# pccasefanctrlx8.net
KiCad netlist of a schematic drawn in EAGLE
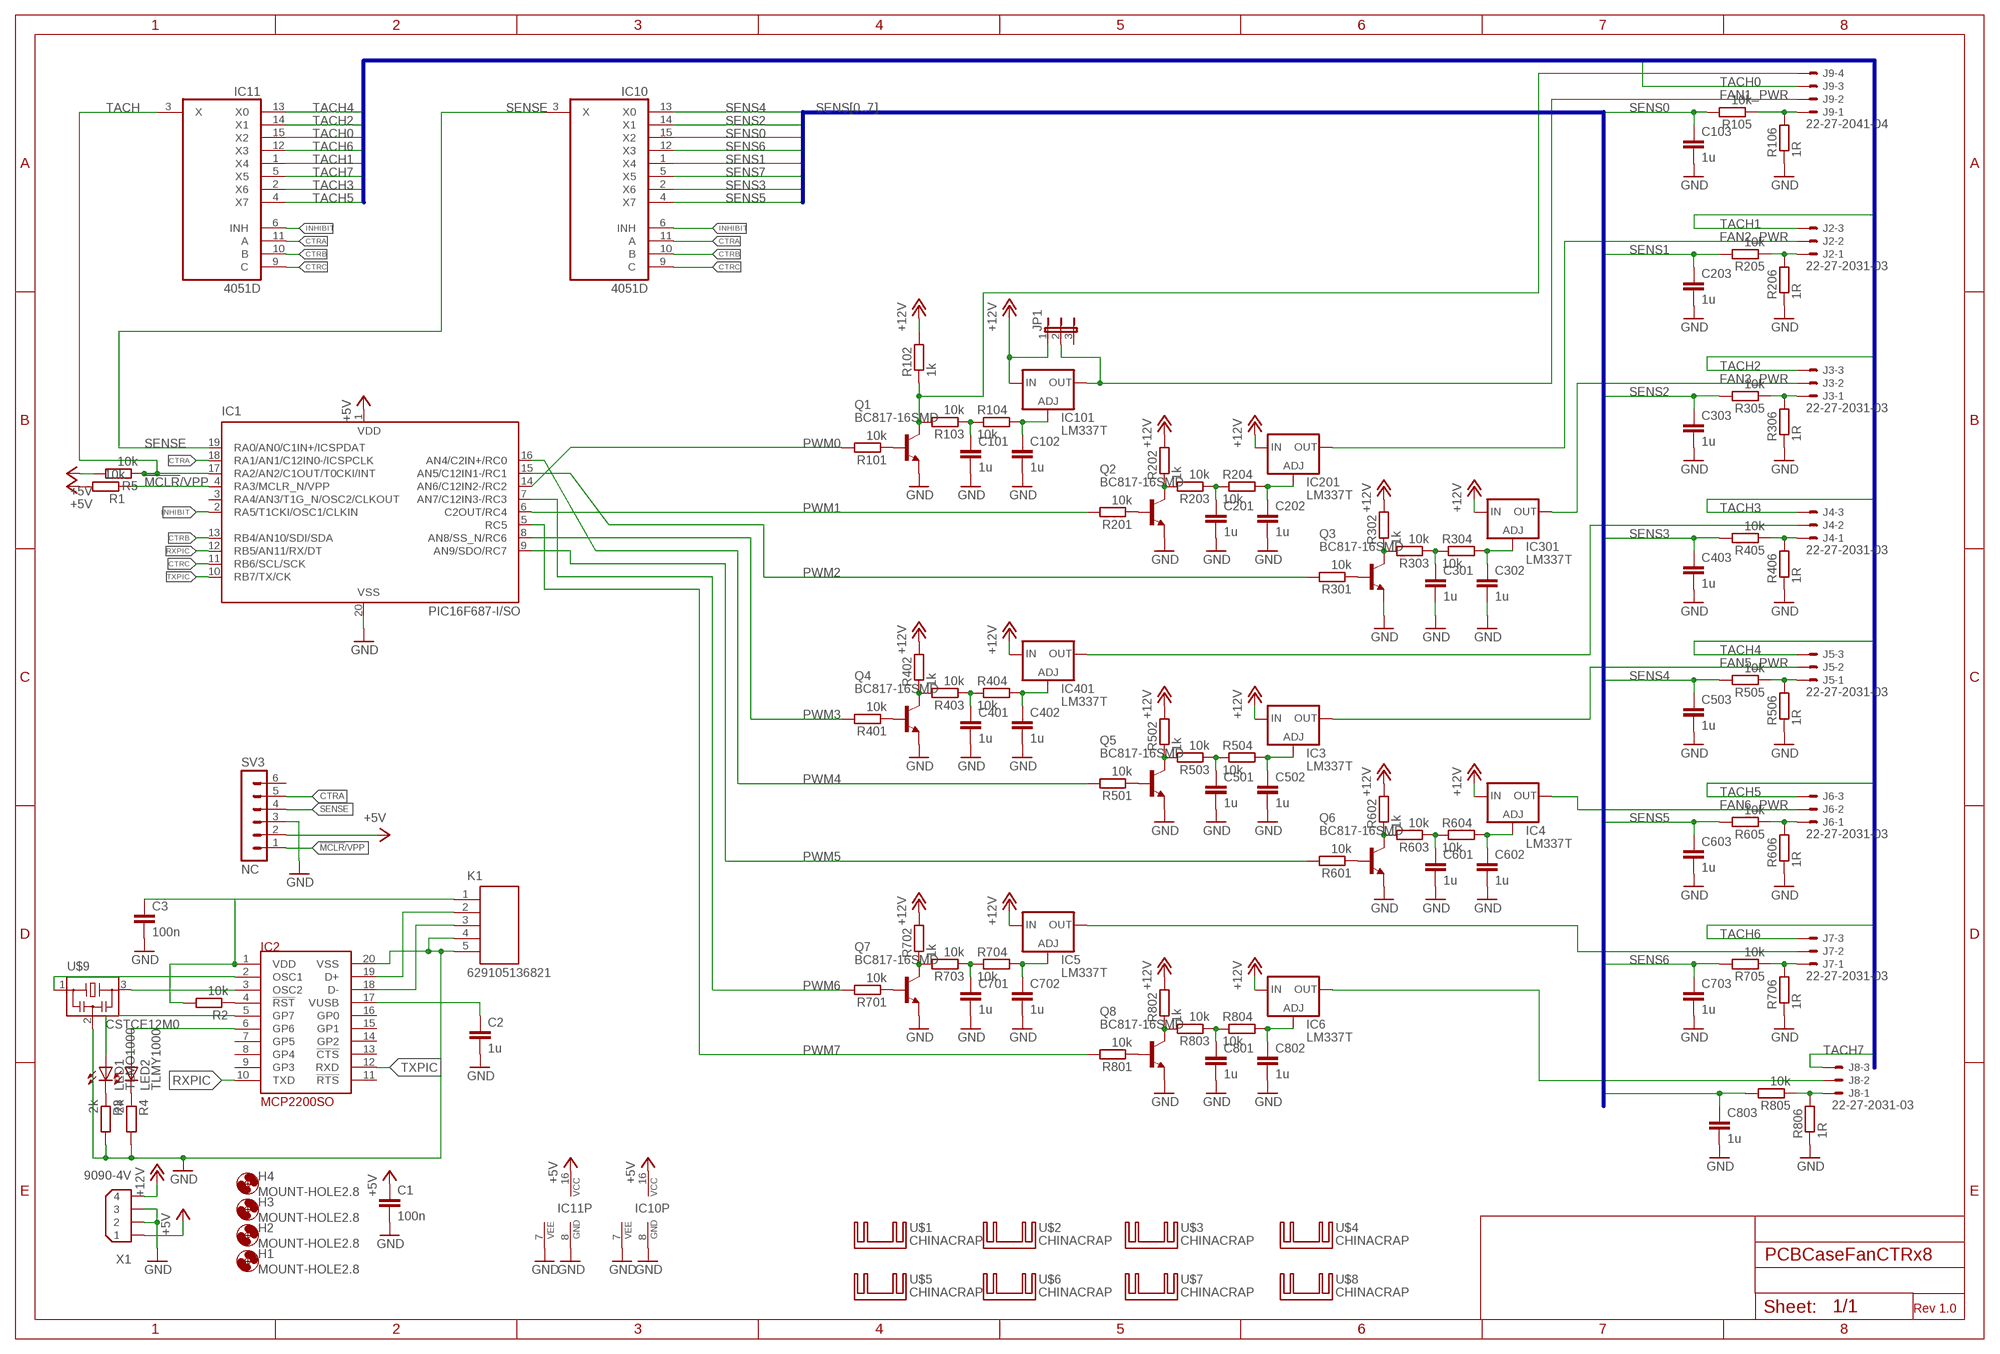
[diagram p0: schematic, sheet 1]

(export (version "E")
  (design (tool "Eeschema 10.0.6"))
  (components
    (comp (ref "C1")
      (value "100n")
      (footprint "eagle-import:C0603K")
      (libsource (lib "eagle-import") (part "C-EUC0603K"))
    )
    (comp (ref "C2")
      (value "1u")
      (footprint "eagle-import:C0603K")
      (libsource (lib "eagle-import") (part "C-EUC0603K"))
    )
    (comp (ref "C3")
      (value "100n")
      (footprint "eagle-import:C0603K")
      (libsource (lib "eagle-import") (part "C-EUC0603K"))
    )
    (comp (ref "C101")
      (value "1u")
      (footprint "eagle-import:C0603K")
      (libsource (lib "eagle-import") (part "C-EUC0603K"))
    )
    (comp (ref "C102")
      (value "1u")
      (footprint "eagle-import:C0603K")
      (libsource (lib "eagle-import") (part "C-EUC0603K"))
    )
    (comp (ref "C103")
      (value "1u")
      (footprint "eagle-import:C0603K")
      (libsource (lib "eagle-import") (part "C-EUC0603K"))
    )
    (comp (ref "C201")
      (value "1u")
      (footprint "eagle-import:C0603K")
      (libsource (lib "eagle-import") (part "C-EUC0603K"))
    )
    (comp (ref "C202")
      (value "1u")
      (footprint "eagle-import:C0603K")
      (libsource (lib "eagle-import") (part "C-EUC0603K"))
    )
    (comp (ref "C203")
      (value "1u")
      (footprint "eagle-import:C0603K")
      (libsource (lib "eagle-import") (part "C-EUC0603K"))
    )
    (comp (ref "C301")
      (value "1u")
      (footprint "eagle-import:C0603K")
      (libsource (lib "eagle-import") (part "C-EUC0603K"))
    )
    (comp (ref "C302")
      (value "1u")
      (footprint "eagle-import:C0603K")
      (libsource (lib "eagle-import") (part "C-EUC0603K"))
    )
    (comp (ref "C303")
      (value "1u")
      (footprint "eagle-import:C0603K")
      (libsource (lib "eagle-import") (part "C-EUC0603K"))
    )
    (comp (ref "C401")
      (value "1u")
      (footprint "eagle-import:C0603K")
      (libsource (lib "eagle-import") (part "C-EUC0603K"))
    )
    (comp (ref "C402")
      (value "1u")
      (footprint "eagle-import:C0603K")
      (libsource (lib "eagle-import") (part "C-EUC0603K"))
    )
    (comp (ref "C403")
      (value "1u")
      (footprint "eagle-import:C0603K")
      (libsource (lib "eagle-import") (part "C-EUC0603K"))
    )
    (comp (ref "C501")
      (value "1u")
      (footprint "eagle-import:C0603K")
      (libsource (lib "eagle-import") (part "C-EUC0603K"))
    )
    (comp (ref "C502")
      (value "1u")
      (footprint "eagle-import:C0603K")
      (libsource (lib "eagle-import") (part "C-EUC0603K"))
    )
    (comp (ref "C503")
      (value "1u")
      (footprint "eagle-import:C0603K")
      (libsource (lib "eagle-import") (part "C-EUC0603K"))
    )
    (comp (ref "C601")
      (value "1u")
      (footprint "eagle-import:C0603K")
      (libsource (lib "eagle-import") (part "C-EUC0603K"))
    )
    (comp (ref "C602")
      (value "1u")
      (footprint "eagle-import:C0603K")
      (libsource (lib "eagle-import") (part "C-EUC0603K"))
    )
    (comp (ref "C603")
      (value "1u")
      (footprint "eagle-import:C0603K")
      (libsource (lib "eagle-import") (part "C-EUC0603K"))
    )
    (comp (ref "C701")
      (value "1u")
      (footprint "eagle-import:C0603K")
      (libsource (lib "eagle-import") (part "C-EUC0603K"))
    )
    (comp (ref "C702")
      (value "1u")
      (footprint "eagle-import:C0603K")
      (libsource (lib "eagle-import") (part "C-EUC0603K"))
    )
    (comp (ref "C703")
      (value "1u")
      (footprint "eagle-import:C0603K")
      (libsource (lib "eagle-import") (part "C-EUC0603K"))
    )
    (comp (ref "C801")
      (value "1u")
      (footprint "eagle-import:C0603K")
      (libsource (lib "eagle-import") (part "C-EUC0603K"))
    )
    (comp (ref "C802")
      (value "1u")
      (footprint "eagle-import:C0603K")
      (libsource (lib "eagle-import") (part "C-EUC0603K"))
    )
    (comp (ref "C803")
      (value "1u")
      (footprint "eagle-import:C0603K")
      (libsource (lib "eagle-import") (part "C-EUC0603K"))
    )
    (comp (ref "H1")
      (value "MOUNT-HOLE2.8")
      (footprint "eagle-import:2,8")
      (libsource (lib "eagle-import") (part "MOUNT-HOLE2.8"))
    )
    (comp (ref "H2")
      (value "MOUNT-HOLE2.8")
      (footprint "eagle-import:2,8")
      (libsource (lib "eagle-import") (part "MOUNT-HOLE2.8"))
    )
    (comp (ref "H3")
      (value "MOUNT-HOLE2.8")
      (footprint "eagle-import:2,8")
      (libsource (lib "eagle-import") (part "MOUNT-HOLE2.8"))
    )
    (comp (ref "H4")
      (value "MOUNT-HOLE2.8")
      (footprint "eagle-import:2,8")
      (libsource (lib "eagle-import") (part "MOUNT-HOLE2.8"))
    )
    (comp (ref "IC1")
      (value "PIC16F687-I/SO")
      (footprint "eagle-import:SO-20W")
      (libsource (lib "eagle-import") (part "PIC16F687-I/SO"))
    )
    (comp (ref "IC2")
      (value "MCP2200SO")
      (footprint "eagle-import:SO-20W")
      (libsource (lib "eagle-import") (part "MCP2200SO"))
    )
    (comp (ref "IC3")
      (value "LM337T")
      (footprint "eagle-import:317TS")
      (libsource (lib "eagle-import") (part "LM317TS"))
    )
    (comp (ref "IC4")
      (value "LM337T")
      (footprint "eagle-import:317TS")
      (libsource (lib "eagle-import") (part "LM317TS"))
    )
    (comp (ref "IC5")
      (value "LM337T")
      (footprint "eagle-import:317TS")
      (libsource (lib "eagle-import") (part "LM317TS"))
    )
    (comp (ref "IC6")
      (value "LM337T")
      (footprint "eagle-import:317TS")
      (libsource (lib "eagle-import") (part "LM317TS"))
    )
    (comp (ref "IC10")
      (value "4051D")
      (footprint "eagle-import:SO16")
      (libsource (lib "eagle-import") (part "4051D"))
    )
    (comp (ref "IC11")
      (value "4051D")
      (footprint "eagle-import:SO16")
      (libsource (lib "eagle-import") (part "4051D"))
    )
    (comp (ref "IC101")
      (value "LM337T")
      (footprint "eagle-import:317TS")
      (libsource (lib "eagle-import") (part "LM317TS"))
    )
    (comp (ref "IC201")
      (value "LM337T")
      (footprint "eagle-import:317TS")
      (libsource (lib "eagle-import") (part "LM317TS"))
    )
    (comp (ref "IC301")
      (value "LM337T")
      (footprint "eagle-import:317TS")
      (libsource (lib "eagle-import") (part "LM317TS"))
    )
    (comp (ref "IC401")
      (value "LM337T")
      (footprint "eagle-import:317TS")
      (libsource (lib "eagle-import") (part "LM317TS"))
    )
    (comp (ref "J2")
      (value "22-27-2031-03")
      (footprint "eagle-import:6410-03")
      (libsource (lib "eagle-import") (part "22-?-0327-2031"))
    )
    (comp (ref "J3")
      (value "22-27-2031-03")
      (footprint "eagle-import:6410-03")
      (libsource (lib "eagle-import") (part "22-?-0327-2031"))
    )
    (comp (ref "J4")
      (value "22-27-2031-03")
      (footprint "eagle-import:6410-03")
      (libsource (lib "eagle-import") (part "22-?-0327-2031"))
    )
    (comp (ref "J5")
      (value "22-27-2031-03")
      (footprint "eagle-import:6410-03")
      (libsource (lib "eagle-import") (part "22-?-0327-2031"))
    )
    (comp (ref "J6")
      (value "22-27-2031-03")
      (footprint "eagle-import:6410-03")
      (libsource (lib "eagle-import") (part "22-?-0327-2031"))
    )
    (comp (ref "J7")
      (value "22-27-2031-03")
      (footprint "eagle-import:6410-03")
      (libsource (lib "eagle-import") (part "22-?-0327-2031"))
    )
    (comp (ref "J8")
      (value "22-27-2031-03")
      (footprint "eagle-import:6410-03")
      (libsource (lib "eagle-import") (part "22-?-0327-2031"))
    )
    (comp (ref "J9")
      (value "22-27-2041-04")
      (footprint "eagle-import:6410-04")
      (libsource (lib "eagle-import") (part "22-?-0427-2041"))
    )
    (comp (ref "JP1")
      (value "JP2E")
      (footprint "eagle-import:JP2")
      (libsource (lib "eagle-import") (part "JP2E"))
    )
    (comp (ref "K1")
      (value "629105136821")
      (footprint "eagle-import:629105136821")
      (libsource (lib "eagle-import") (part "629105136821"))
    )
    (comp (ref "LED1")
      (value "TLMO1000")
      (footprint "eagle-import:SML0603")
      (libsource (lib "eagle-import") (part "LEDSML0603"))
    )
    (comp (ref "LED2")
      (value "TLMY1000")
      (footprint "eagle-import:SML0603")
      (libsource (lib "eagle-import") (part "LEDSML0603"))
    )
    (comp (ref "Q1")
      (value "BC817-16SMD")
      (footprint "eagle-import:SOT23-BEC")
      (libsource (lib "eagle-import") (part "BC817SMD-16"))
    )
    (comp (ref "Q2")
      (value "BC817-16SMD")
      (footprint "eagle-import:SOT23-BEC")
      (libsource (lib "eagle-import") (part "BC817SMD-16"))
    )
    (comp (ref "Q3")
      (value "BC817-16SMD")
      (footprint "eagle-import:SOT23-BEC")
      (libsource (lib "eagle-import") (part "BC817SMD-16"))
    )
    (comp (ref "Q4")
      (value "BC817-16SMD")
      (footprint "eagle-import:SOT23-BEC")
      (libsource (lib "eagle-import") (part "BC817SMD-16"))
    )
    (comp (ref "Q5")
      (value "BC817-16SMD")
      (footprint "eagle-import:SOT23-BEC")
      (libsource (lib "eagle-import") (part "BC817SMD-16"))
    )
    (comp (ref "Q6")
      (value "BC817-16SMD")
      (footprint "eagle-import:SOT23-BEC")
      (libsource (lib "eagle-import") (part "BC817SMD-16"))
    )
    (comp (ref "Q7")
      (value "BC817-16SMD")
      (footprint "eagle-import:SOT23-BEC")
      (libsource (lib "eagle-import") (part "BC817SMD-16"))
    )
    (comp (ref "Q8")
      (value "BC817-16SMD")
      (footprint "eagle-import:SOT23-BEC")
      (libsource (lib "eagle-import") (part "BC817SMD-16"))
    )
    (comp (ref "R1")
      (value "10k")
      (footprint "eagle-import:R0603")
      (libsource (lib "eagle-import") (part "R-EU_R0603"))
    )
    (comp (ref "R2")
      (value "10k")
      (footprint "eagle-import:R0603")
      (libsource (lib "eagle-import") (part "R-EU_R0603"))
    )
    (comp (ref "R3")
      (value "2k")
      (footprint "eagle-import:R0603")
      (libsource (lib "eagle-import") (part "R-EU_R0603"))
    )
    (comp (ref "R4")
      (value "2k")
      (footprint "eagle-import:R0603")
      (libsource (lib "eagle-import") (part "R-EU_R0603"))
    )
    (comp (ref "R5")
      (value "10k")
      (footprint "eagle-import:R0603")
      (libsource (lib "eagle-import") (part "R-EU_R0603"))
    )
    (comp (ref "R101")
      (value "10k")
      (footprint "eagle-import:R0603")
      (libsource (lib "eagle-import") (part "R-EU_R0603"))
    )
    (comp (ref "R102")
      (value "1k")
      (footprint "eagle-import:R0603")
      (libsource (lib "eagle-import") (part "R-EU_R0603"))
    )
    (comp (ref "R103")
      (value "10k")
      (footprint "eagle-import:R0603")
      (libsource (lib "eagle-import") (part "R-EU_R0603"))
    )
    (comp (ref "R104")
      (value "10k")
      (footprint "eagle-import:R0603")
      (libsource (lib "eagle-import") (part "R-EU_R0603"))
    )
    (comp (ref "R105")
      (value "10k")
      (footprint "eagle-import:R0603")
      (libsource (lib "eagle-import") (part "R-EU_R0603"))
    )
    (comp (ref "R106")
      (value "1R")
      (footprint "eagle-import:P0613V")
      (libsource (lib "eagle-import") (part "R-EU_0613/5V"))
    )
    (comp (ref "R201")
      (value "10k")
      (footprint "eagle-import:R0603")
      (libsource (lib "eagle-import") (part "R-EU_R0603"))
    )
    (comp (ref "R202")
      (value "1k")
      (footprint "eagle-import:R0603")
      (libsource (lib "eagle-import") (part "R-EU_R0603"))
    )
    (comp (ref "R203")
      (value "10k")
      (footprint "eagle-import:R0603")
      (libsource (lib "eagle-import") (part "R-EU_R0603"))
    )
    (comp (ref "R204")
      (value "10k")
      (footprint "eagle-import:R0603")
      (libsource (lib "eagle-import") (part "R-EU_R0603"))
    )
    (comp (ref "R205")
      (value "10k")
      (footprint "eagle-import:R0603")
      (libsource (lib "eagle-import") (part "R-EU_R0603"))
    )
    (comp (ref "R206")
      (value "1R")
      (footprint "eagle-import:P0613V")
      (libsource (lib "eagle-import") (part "R-EU_0613/5V"))
    )
    (comp (ref "R301")
      (value "10k")
      (footprint "eagle-import:R0603")
      (libsource (lib "eagle-import") (part "R-EU_R0603"))
    )
    (comp (ref "R302")
      (value "1k")
      (footprint "eagle-import:R0603")
      (libsource (lib "eagle-import") (part "R-EU_R0603"))
    )
    (comp (ref "R303")
      (value "10k")
      (footprint "eagle-import:R0603")
      (libsource (lib "eagle-import") (part "R-EU_R0603"))
    )
    (comp (ref "R304")
      (value "10k")
      (footprint "eagle-import:R0603")
      (libsource (lib "eagle-import") (part "R-EU_R0603"))
    )
    (comp (ref "R305")
      (value "10k")
      (footprint "eagle-import:R0603")
      (libsource (lib "eagle-import") (part "R-EU_R0603"))
    )
    (comp (ref "R306")
      (value "1R")
      (footprint "eagle-import:P0613V")
      (libsource (lib "eagle-import") (part "R-EU_0613/5V"))
    )
    (comp (ref "R401")
      (value "10k")
      (footprint "eagle-import:R0603")
      (libsource (lib "eagle-import") (part "R-EU_R0603"))
    )
    (comp (ref "R402")
      (value "1k")
      (footprint "eagle-import:R0603")
      (libsource (lib "eagle-import") (part "R-EU_R0603"))
    )
    (comp (ref "R403")
      (value "10k")
      (footprint "eagle-import:R0603")
      (libsource (lib "eagle-import") (part "R-EU_R0603"))
    )
    (comp (ref "R404")
      (value "10k")
      (footprint "eagle-import:R0603")
      (libsource (lib "eagle-import") (part "R-EU_R0603"))
    )
    (comp (ref "R405")
      (value "10k")
      (footprint "eagle-import:R0603")
      (libsource (lib "eagle-import") (part "R-EU_R0603"))
    )
    (comp (ref "R406")
      (value "1R")
      (footprint "eagle-import:P0613V")
      (libsource (lib "eagle-import") (part "R-EU_0613/5V"))
    )
    (comp (ref "R501")
      (value "10k")
      (footprint "eagle-import:R0603")
      (libsource (lib "eagle-import") (part "R-EU_R0603"))
    )
    (comp (ref "R502")
      (value "1k")
      (footprint "eagle-import:R0603")
      (libsource (lib "eagle-import") (part "R-EU_R0603"))
    )
    (comp (ref "R503")
      (value "10k")
      (footprint "eagle-import:R0603")
      (libsource (lib "eagle-import") (part "R-EU_R0603"))
    )
    (comp (ref "R504")
      (value "10k")
      (footprint "eagle-import:R0603")
      (libsource (lib "eagle-import") (part "R-EU_R0603"))
    )
    (comp (ref "R505")
      (value "10k")
      (footprint "eagle-import:R0603")
      (libsource (lib "eagle-import") (part "R-EU_R0603"))
    )
    (comp (ref "R506")
      (value "1R")
      (footprint "eagle-import:P0613V")
      (libsource (lib "eagle-import") (part "R-EU_0613/5V"))
    )
    (comp (ref "R601")
      (value "10k")
      (footprint "eagle-import:R0603")
      (libsource (lib "eagle-import") (part "R-EU_R0603"))
    )
    (comp (ref "R602")
      (value "1k")
      (footprint "eagle-import:R0603")
      (libsource (lib "eagle-import") (part "R-EU_R0603"))
    )
    (comp (ref "R603")
      (value "10k")
      (footprint "eagle-import:R0603")
      (libsource (lib "eagle-import") (part "R-EU_R0603"))
    )
    (comp (ref "R604")
      (value "10k")
      (footprint "eagle-import:R0603")
      (libsource (lib "eagle-import") (part "R-EU_R0603"))
    )
    (comp (ref "R605")
      (value "10k")
      (footprint "eagle-import:R0603")
      (libsource (lib "eagle-import") (part "R-EU_R0603"))
    )
    (comp (ref "R606")
      (value "1R")
      (footprint "eagle-import:P0613V")
      (libsource (lib "eagle-import") (part "R-EU_0613/5V"))
    )
    (comp (ref "R701")
      (value "10k")
      (footprint "eagle-import:R0603")
      (libsource (lib "eagle-import") (part "R-EU_R0603"))
    )
    (comp (ref "R702")
      (value "1k")
      (footprint "eagle-import:R0603")
      (libsource (lib "eagle-import") (part "R-EU_R0603"))
    )
    (comp (ref "R703")
      (value "10k")
      (footprint "eagle-import:R0603")
      (libsource (lib "eagle-import") (part "R-EU_R0603"))
    )
    (comp (ref "R704")
      (value "10k")
      (footprint "eagle-import:R0603")
      (libsource (lib "eagle-import") (part "R-EU_R0603"))
    )
    (comp (ref "R705")
      (value "10k")
      (footprint "eagle-import:R0603")
      (libsource (lib "eagle-import") (part "R-EU_R0603"))
    )
    (comp (ref "R706")
      (value "1R")
      (footprint "eagle-import:P0613V")
      (libsource (lib "eagle-import") (part "R-EU_0613/5V"))
    )
    (comp (ref "R801")
      (value "10k")
      (footprint "eagle-import:R0603")
      (libsource (lib "eagle-import") (part "R-EU_R0603"))
    )
    (comp (ref "R802")
      (value "1k")
      (footprint "eagle-import:R0603")
      (libsource (lib "eagle-import") (part "R-EU_R0603"))
    )
    (comp (ref "R803")
      (value "10k")
      (footprint "eagle-import:R0603")
      (libsource (lib "eagle-import") (part "R-EU_R0603"))
    )
    (comp (ref "R804")
      (value "10k")
      (footprint "eagle-import:R0603")
      (libsource (lib "eagle-import") (part "R-EU_R0603"))
    )
    (comp (ref "R805")
      (value "10k")
      (footprint "eagle-import:R0603")
      (libsource (lib "eagle-import") (part "R-EU_R0603"))
    )
    (comp (ref "R806")
      (value "1R")
      (footprint "eagle-import:P0613V")
      (libsource (lib "eagle-import") (part "R-EU_0613/5V"))
    )
    (comp (ref "SV3")
      (value "NC")
      (footprint "eagle-import:MA06-1")
      (libsource (lib "eagle-import") (part "MA06-1"))
    )
    (comp (ref "U$1")
      (value "CHINACRAP")
      (footprint "eagle-import:MYCHINACRAP")
      (libsource (lib "eagle-import") (part "CHINACRAP"))
    )
    (comp (ref "U$2")
      (value "CHINACRAP")
      (footprint "eagle-import:MYCHINACRAP")
      (libsource (lib "eagle-import") (part "CHINACRAP"))
    )
    (comp (ref "U$3")
      (value "CHINACRAP")
      (footprint "eagle-import:MYCHINACRAP")
      (libsource (lib "eagle-import") (part "CHINACRAP"))
    )
    (comp (ref "U$4")
      (value "CHINACRAP")
      (footprint "eagle-import:MYCHINACRAP")
      (libsource (lib "eagle-import") (part "CHINACRAP"))
    )
    (comp (ref "U$5")
      (value "CHINACRAP")
      (footprint "eagle-import:MYCHINACRAP")
      (libsource (lib "eagle-import") (part "CHINACRAP"))
    )
    (comp (ref "U$6")
      (value "CHINACRAP")
      (footprint "eagle-import:MYCHINACRAP")
      (libsource (lib "eagle-import") (part "CHINACRAP"))
    )
    (comp (ref "U$7")
      (value "CHINACRAP")
      (footprint "eagle-import:MYCHINACRAP")
      (libsource (lib "eagle-import") (part "CHINACRAP"))
    )
    (comp (ref "U$8")
      (value "CHINACRAP")
      (footprint "eagle-import:MYCHINACRAP")
      (libsource (lib "eagle-import") (part "CHINACRAP"))
    )
    (comp (ref "U$9")
      (value "CSTCE12M0")
      (footprint "eagle-import:CSTCE_G")
      (libsource (lib "eagle-import") (part "CSTCE12M0"))
    )
    (comp (ref "X1")
      (value "9090-4V")
      (footprint "eagle-import:9090-4V")
      (libsource (lib "eagle-import") (part "9090-4V"))
    )
  )
  (nets
    (net (code "1") (name "+5V") (class "Default")
      (node (ref "C1") (pin "1") (pinfunction "1_1") (pintype "passive"))
      (node (ref "IC1") (pin "1") (pinfunction "VDD_1") (pintype "power_in"))
      (node (ref "IC10") (pin "16") (pinfunction "VCC_16") (pintype "power_in"))
      (node (ref "IC11") (pin "16") (pinfunction "VCC_16") (pintype "power_in"))
      (node (ref "R1") (pin "2") (pinfunction "2_2") (pintype "passive"))
      (node (ref "R5") (pin "2") (pinfunction "2_2") (pintype "passive"))
      (node (ref "SV3") (pin "2") (pinfunction "2_2") (pintype "passive"))
      (node (ref "X1") (pin "1") (pinfunction "1_1") (pintype "passive"))
    )
    (net (code "2") (name "+12V") (class "Default")
      (node (ref "IC101") (pin "3") (pinfunction "IN_3") (pintype "input"))
      (node (ref "IC201") (pin "3") (pinfunction "IN_3") (pintype "input"))
      (node (ref "IC3") (pin "3") (pinfunction "IN_3") (pintype "input"))
      (node (ref "IC301") (pin "3") (pinfunction "IN_3") (pintype "input"))
      (node (ref "IC4") (pin "3") (pinfunction "IN_3") (pintype "input"))
      (node (ref "IC401") (pin "3") (pinfunction "IN_3") (pintype "input"))
      (node (ref "IC5") (pin "3") (pinfunction "IN_3") (pintype "input"))
      (node (ref "IC6") (pin "3") (pinfunction "IN_3") (pintype "input"))
      (node (ref "JP1") (pin "1") (pinfunction "1_1") (pintype "passive"))
      (node (ref "R102") (pin "2") (pinfunction "2_2") (pintype "passive"))
      (node (ref "R202") (pin "2") (pinfunction "2_2") (pintype "passive"))
      (node (ref "R302") (pin "2") (pinfunction "2_2") (pintype "passive"))
      (node (ref "R402") (pin "2") (pinfunction "2_2") (pintype "passive"))
      (node (ref "R502") (pin "2") (pinfunction "2_2") (pintype "passive"))
      (node (ref "R602") (pin "2") (pinfunction "2_2") (pintype "passive"))
      (node (ref "R702") (pin "2") (pinfunction "2_2") (pintype "passive"))
      (node (ref "R802") (pin "2") (pinfunction "2_2") (pintype "passive"))
      (node (ref "X1") (pin "4") (pinfunction "4_4") (pintype "passive"))
    )
    (net (code "3") (name "/FAN1_PWR") (class "Default")
      (node (ref "IC101") (pin "2") (pinfunction "OUT_2") (pintype "passive"))
      (node (ref "J9") (pin "2") (pinfunction "S_2") (pintype "passive"))
      (node (ref "JP1") (pin "2") (pinfunction "2_2") (pintype "passive"))
    )
    (net (code "4") (name "/FAN2_PWR") (class "Default")
      (node (ref "IC201") (pin "2") (pinfunction "OUT_2") (pintype "passive"))
      (node (ref "J2") (pin "2") (pinfunction "S_2") (pintype "passive"))
    )
    (net (code "5") (name "/FAN3_PWR") (class "Default")
      (node (ref "IC301") (pin "2") (pinfunction "OUT_2") (pintype "passive"))
      (node (ref "J3") (pin "2") (pinfunction "S_2") (pintype "passive"))
    )
    (net (code "6") (name "/FAN5_PWR") (class "Default")
      (node (ref "IC3") (pin "2") (pinfunction "OUT_2") (pintype "passive"))
      (node (ref "J5") (pin "2") (pinfunction "S_2") (pintype "passive"))
    )
    (net (code "7") (name "/FAN6_PWR") (class "Default")
      (node (ref "IC4") (pin "2") (pinfunction "OUT_2") (pintype "passive"))
      (node (ref "J6") (pin "2") (pinfunction "S_2") (pintype "passive"))
    )
    (net (code "8") (name "/PWM0") (class "Default")
      (node (ref "IC1") (pin "14") (pinfunction "AN6/C12IN2-/RC2_14") (pintype "bidirectional"))
      (node (ref "R101") (pin "2") (pinfunction "2_2") (pintype "passive"))
    )
    (net (code "9") (name "/PWM1") (class "Default")
      (node (ref "IC1") (pin "6") (pinfunction "C2OUT/RC4_6") (pintype "bidirectional"))
      (node (ref "R201") (pin "2") (pinfunction "2_2") (pintype "passive"))
    )
    (net (code "10") (name "/PWM2") (class "Default")
      (node (ref "IC1") (pin "15") (pinfunction "AN5/C12IN1-/RC1_15") (pintype "bidirectional"))
      (node (ref "R301") (pin "2") (pinfunction "2_2") (pintype "passive"))
    )
    (net (code "11") (name "/PWM3") (class "Default")
      (node (ref "IC1") (pin "8") (pinfunction "AN8/SS_N/RC6_8") (pintype "bidirectional"))
      (node (ref "R401") (pin "2") (pinfunction "2_2") (pintype "passive"))
    )
    (net (code "12") (name "/PWM4") (class "Default")
      (node (ref "IC1") (pin "16") (pinfunction "AN4/C2IN+/RC0_16") (pintype "bidirectional"))
      (node (ref "R501") (pin "2") (pinfunction "2_2") (pintype "passive"))
    )
    (net (code "13") (name "/PWM5") (class "Default")
      (node (ref "IC1") (pin "9") (pinfunction "AN9/SDO/RC7_9") (pintype "bidirectional"))
      (node (ref "R601") (pin "2") (pinfunction "2_2") (pintype "passive"))
    )
    (net (code "14") (name "/PWM6") (class "Default")
      (node (ref "IC1") (pin "7") (pinfunction "AN7/C12IN3-/RC3_7") (pintype "bidirectional"))
      (node (ref "R701") (pin "2") (pinfunction "2_2") (pintype "passive"))
    )
    (net (code "15") (name "/PWM7") (class "Default")
      (node (ref "IC1") (pin "5") (pinfunction "RC5_5") (pintype "bidirectional"))
      (node (ref "R801") (pin "2") (pinfunction "2_2") (pintype "passive"))
    )
    (net (code "16") (name "/SENS0") (class "Default")
      (node (ref "C103") (pin "1") (pinfunction "1_1") (pintype "passive"))
      (node (ref "IC10") (pin "15") (pinfunction "X2_15") (pintype "bidirectional"))
      (node (ref "R105") (pin "2") (pinfunction "2_2") (pintype "passive"))
    )
    (net (code "17") (name "/SENS1") (class "Default")
      (node (ref "C203") (pin "1") (pinfunction "1_1") (pintype "passive"))
      (node (ref "IC10") (pin "1") (pinfunction "X4_1") (pintype "bidirectional"))
      (node (ref "R205") (pin "2") (pinfunction "2_2") (pintype "passive"))
    )
    (net (code "18") (name "/SENS2") (class "Default")
      (node (ref "C303") (pin "1") (pinfunction "1_1") (pintype "passive"))
      (node (ref "IC10") (pin "14") (pinfunction "X1_14") (pintype "bidirectional"))
      (node (ref "R305") (pin "2") (pinfunction "2_2") (pintype "passive"))
    )
    (net (code "19") (name "/SENS3") (class "Default")
      (node (ref "C403") (pin "1") (pinfunction "1_1") (pintype "passive"))
      (node (ref "IC10") (pin "2") (pinfunction "X6_2") (pintype "bidirectional"))
      (node (ref "R405") (pin "2") (pinfunction "2_2") (pintype "passive"))
    )
    (net (code "20") (name "/SENS4") (class "Default")
      (node (ref "C503") (pin "1") (pinfunction "1_1") (pintype "passive"))
      (node (ref "IC10") (pin "13") (pinfunction "X0_13") (pintype "bidirectional"))
      (node (ref "R505") (pin "2") (pinfunction "2_2") (pintype "passive"))
    )
    (net (code "21") (name "/SENS5") (class "Default")
      (node (ref "C603") (pin "1") (pinfunction "1_1") (pintype "passive"))
      (node (ref "IC10") (pin "4") (pinfunction "X7_4") (pintype "bidirectional"))
      (node (ref "R605") (pin "2") (pinfunction "2_2") (pintype "passive"))
    )
    (net (code "22") (name "/SENS6") (class "Default")
      (node (ref "C703") (pin "1") (pinfunction "1_1") (pintype "passive"))
      (node (ref "IC10") (pin "12") (pinfunction "X3_12") (pintype "bidirectional"))
      (node (ref "R705") (pin "2") (pinfunction "2_2") (pintype "passive"))
    )
    (net (code "23") (name "/SENS7") (class "Default")
      (node (ref "C803") (pin "1") (pinfunction "1_1") (pintype "passive"))
      (node (ref "IC10") (pin "5") (pinfunction "X5_5") (pintype "bidirectional"))
      (node (ref "R805") (pin "2") (pinfunction "2_2") (pintype "passive"))
    )
    (net (code "25") (name "/TACH") (class "Default")
      (node (ref "IC1") (pin "17") (pinfunction "RA2/AN2/C1OUT/T0CKI/INT_17") (pintype "bidirectional"))
      (node (ref "IC11") (pin "3") (pinfunction "X_3") (pintype "bidirectional"))
      (node (ref "R5") (pin "1") (pinfunction "1_1") (pintype "passive"))
    )
    (net (code "26") (name "/TACH0") (class "Default")
      (node (ref "IC11") (pin "15") (pinfunction "X2_15") (pintype "bidirectional"))
      (node (ref "J9") (pin "3") (pinfunction "S_3") (pintype "passive"))
    )
    (net (code "27") (name "/TACH1") (class "Default")
      (node (ref "IC11") (pin "1") (pinfunction "X4_1") (pintype "bidirectional"))
      (node (ref "J2") (pin "3") (pinfunction "S_3") (pintype "passive"))
    )
    (net (code "28") (name "/TACH2") (class "Default")
      (node (ref "IC11") (pin "14") (pinfunction "X1_14") (pintype "bidirectional"))
      (node (ref "J3") (pin "3") (pinfunction "S_3") (pintype "passive"))
    )
    (net (code "29") (name "/TACH3") (class "Default")
      (node (ref "IC11") (pin "2") (pinfunction "X6_2") (pintype "bidirectional"))
      (node (ref "J4") (pin "3") (pinfunction "S_3") (pintype "passive"))
    )
    (net (code "30") (name "/TACH4") (class "Default")
      (node (ref "IC11") (pin "13") (pinfunction "X0_13") (pintype "bidirectional"))
      (node (ref "J5") (pin "3") (pinfunction "S_3") (pintype "passive"))
    )
    (net (code "31") (name "/TACH5") (class "Default")
      (node (ref "IC11") (pin "4") (pinfunction "X7_4") (pintype "bidirectional"))
      (node (ref "J6") (pin "3") (pinfunction "S_3") (pintype "passive"))
    )
    (net (code "32") (name "/TACH6") (class "Default")
      (node (ref "IC11") (pin "12") (pinfunction "X3_12") (pintype "bidirectional"))
      (node (ref "J7") (pin "3") (pinfunction "S_3") (pintype "passive"))
    )
    (net (code "33") (name "/TACH7") (class "Default")
      (node (ref "IC11") (pin "5") (pinfunction "X5_5") (pintype "bidirectional"))
      (node (ref "J8") (pin "3") (pinfunction "S_3") (pintype "passive"))
    )
    (net (code "34") (name "/~{MCLR}{slash}VPP") (class "Default")
      (node (ref "IC1") (pin "4") (pinfunction "RA3/MCLR_N/VPP_4") (pintype "input"))
      (node (ref "R1") (pin "1") (pinfunction "1_1") (pintype "passive"))
      (node (ref "SV3") (pin "1") (pinfunction "1_1") (pintype "passive"))
    )
    (net (code "35") (name "CTRA") (class "Default")
      (node (ref "IC1") (pin "18") (pinfunction "RA1/AN1/C12IN0-/ICSPCLK_18") (pintype "bidirectional"))
      (node (ref "IC10") (pin "11") (pinfunction "A_11") (pintype "input"))
      (node (ref "IC11") (pin "11") (pinfunction "A_11") (pintype "input"))
      (node (ref "SV3") (pin "5") (pinfunction "5_5") (pintype "passive"))
    )
    (net (code "36") (name "CTRB") (class "Default")
      (node (ref "IC1") (pin "13") (pinfunction "RB4/AN10/SDI/SDA_13") (pintype "bidirectional"))
      (node (ref "IC10") (pin "10") (pinfunction "B_10") (pintype "input"))
      (node (ref "IC11") (pin "10") (pinfunction "B_10") (pintype "input"))
    )
    (net (code "37") (name "CTRC") (class "Default")
      (node (ref "IC1") (pin "11") (pinfunction "RB6/SCL/SCK_11") (pintype "bidirectional"))
      (node (ref "IC10") (pin "9") (pinfunction "C_9") (pintype "input"))
      (node (ref "IC11") (pin "9") (pinfunction "C_9") (pintype "input"))
    )
    (net (code "38") (name "GND") (class "Default")
      (node (ref "C1") (pin "2") (pinfunction "2_2") (pintype "passive"))
      (node (ref "C101") (pin "2") (pinfunction "2_2") (pintype "passive"))
      (node (ref "C102") (pin "2") (pinfunction "2_2") (pintype "passive"))
      (node (ref "C103") (pin "2") (pinfunction "2_2") (pintype "passive"))
      (node (ref "C2") (pin "2") (pinfunction "2_2") (pintype "passive"))
      (node (ref "C201") (pin "2") (pinfunction "2_2") (pintype "passive"))
      (node (ref "C202") (pin "2") (pinfunction "2_2") (pintype "passive"))
      (node (ref "C203") (pin "2") (pinfunction "2_2") (pintype "passive"))
      (node (ref "C3") (pin "2") (pinfunction "2_2") (pintype "passive"))
      (node (ref "C301") (pin "2") (pinfunction "2_2") (pintype "passive"))
      (node (ref "C302") (pin "2") (pinfunction "2_2") (pintype "passive"))
      (node (ref "C303") (pin "2") (pinfunction "2_2") (pintype "passive"))
      (node (ref "C401") (pin "2") (pinfunction "2_2") (pintype "passive"))
      (node (ref "C402") (pin "2") (pinfunction "2_2") (pintype "passive"))
      (node (ref "C403") (pin "2") (pinfunction "2_2") (pintype "passive"))
      (node (ref "C501") (pin "2") (pinfunction "2_2") (pintype "passive"))
      (node (ref "C502") (pin "2") (pinfunction "2_2") (pintype "passive"))
      (node (ref "C503") (pin "2") (pinfunction "2_2") (pintype "passive"))
      (node (ref "C601") (pin "2") (pinfunction "2_2") (pintype "passive"))
      (node (ref "C602") (pin "2") (pinfunction "2_2") (pintype "passive"))
      (node (ref "C603") (pin "2") (pinfunction "2_2") (pintype "passive"))
      (node (ref "C701") (pin "2") (pinfunction "2_2") (pintype "passive"))
      (node (ref "C702") (pin "2") (pinfunction "2_2") (pintype "passive"))
      (node (ref "C703") (pin "2") (pinfunction "2_2") (pintype "passive"))
      (node (ref "C801") (pin "2") (pinfunction "2_2") (pintype "passive"))
      (node (ref "C802") (pin "2") (pinfunction "2_2") (pintype "passive"))
      (node (ref "C803") (pin "2") (pinfunction "2_2") (pintype "passive"))
      (node (ref "IC1") (pin "20") (pinfunction "VSS_20") (pintype "power_in"))
      (node (ref "IC10") (pin "7") (pinfunction "VEE_7") (pintype "power_in"))
      (node (ref "IC10") (pin "8") (pinfunction "GND_8") (pintype "power_in"))
      (node (ref "IC11") (pin "7") (pinfunction "VEE_7") (pintype "power_in"))
      (node (ref "IC11") (pin "8") (pinfunction "GND_8") (pintype "power_in"))
      (node (ref "IC2") (pin "20") (pinfunction "VSS_20") (pintype "power_in"))
      (node (ref "K1") (pin "4") (pinfunction "4_4") (pintype "passive"))
      (node (ref "K1") (pin "5") (pinfunction "5_5") (pintype "passive"))
      (node (ref "Q1") (pin "E") (pinfunction "E_E") (pintype "passive"))
      (node (ref "Q2") (pin "E") (pinfunction "E_E") (pintype "passive"))
      (node (ref "Q3") (pin "E") (pinfunction "E_E") (pintype "passive"))
      (node (ref "Q4") (pin "E") (pinfunction "E_E") (pintype "passive"))
      (node (ref "Q5") (pin "E") (pinfunction "E_E") (pintype "passive"))
      (node (ref "Q6") (pin "E") (pinfunction "E_E") (pintype "passive"))
      (node (ref "Q7") (pin "E") (pinfunction "E_E") (pintype "passive"))
      (node (ref "Q8") (pin "E") (pinfunction "E_E") (pintype "passive"))
      (node (ref "R106") (pin "1") (pinfunction "1_1") (pintype "passive"))
      (node (ref "R206") (pin "1") (pinfunction "1_1") (pintype "passive"))
      (node (ref "R3") (pin "2") (pinfunction "2_2") (pintype "passive"))
      (node (ref "R306") (pin "1") (pinfunction "1_1") (pintype "passive"))
      (node (ref "R4") (pin "2") (pinfunction "2_2") (pintype "passive"))
      (node (ref "R406") (pin "1") (pinfunction "1_1") (pintype "passive"))
      (node (ref "R506") (pin "1") (pinfunction "1_1") (pintype "passive"))
      (node (ref "R606") (pin "1") (pinfunction "1_1") (pintype "passive"))
      (node (ref "R706") (pin "1") (pinfunction "1_1") (pintype "passive"))
      (node (ref "R806") (pin "1") (pinfunction "1_1") (pintype "passive"))
      (node (ref "SV3") (pin "3") (pinfunction "3_3") (pintype "passive"))
      (node (ref "U$9") (pin "2") (pinfunction "2_2") (pintype "passive"))
      (node (ref "X1") (pin "2") (pinfunction "2_2") (pintype "passive"))
      (node (ref "X1") (pin "3") (pinfunction "3_3") (pintype "passive"))
    )
    (net (code "39") (name "INHIBIT") (class "Default")
      (node (ref "IC1") (pin "2") (pinfunction "RA5/T1CKI/OSC1/CLKIN_2") (pintype "bidirectional"))
      (node (ref "IC10") (pin "6") (pinfunction "INH_6") (pintype "input"))
      (node (ref "IC11") (pin "6") (pinfunction "INH_6") (pintype "input"))
    )
    (net (code "40") (name "Net-(C101-Pad1)") (class "Default")
      (node (ref "C101") (pin "1") (pinfunction "1_1") (pintype "passive"))
      (node (ref "R103") (pin "1") (pinfunction "1_1") (pintype "passive"))
      (node (ref "R104") (pin "1") (pinfunction "1_1") (pintype "passive"))
    )
    (net (code "41") (name "Net-(C201-Pad1)") (class "Default")
      (node (ref "C201") (pin "1") (pinfunction "1_1") (pintype "passive"))
      (node (ref "R203") (pin "1") (pinfunction "1_1") (pintype "passive"))
      (node (ref "R204") (pin "1") (pinfunction "1_1") (pintype "passive"))
    )
    (net (code "42") (name "Net-(C301-Pad1)") (class "Default")
      (node (ref "C301") (pin "1") (pinfunction "1_1") (pintype "passive"))
      (node (ref "R303") (pin "1") (pinfunction "1_1") (pintype "passive"))
      (node (ref "R304") (pin "1") (pinfunction "1_1") (pintype "passive"))
    )
    (net (code "43") (name "Net-(C401-Pad1)") (class "Default")
      (node (ref "C401") (pin "1") (pinfunction "1_1") (pintype "passive"))
      (node (ref "R403") (pin "1") (pinfunction "1_1") (pintype "passive"))
      (node (ref "R404") (pin "1") (pinfunction "1_1") (pintype "passive"))
    )
    (net (code "44") (name "Net-(C501-Pad1)") (class "Default")
      (node (ref "C501") (pin "1") (pinfunction "1_1") (pintype "passive"))
      (node (ref "R503") (pin "1") (pinfunction "1_1") (pintype "passive"))
      (node (ref "R504") (pin "1") (pinfunction "1_1") (pintype "passive"))
    )
    (net (code "45") (name "Net-(C601-Pad1)") (class "Default")
      (node (ref "C601") (pin "1") (pinfunction "1_1") (pintype "passive"))
      (node (ref "R603") (pin "1") (pinfunction "1_1") (pintype "passive"))
      (node (ref "R604") (pin "1") (pinfunction "1_1") (pintype "passive"))
    )
    (net (code "46") (name "Net-(C701-Pad1)") (class "Default")
      (node (ref "C701") (pin "1") (pinfunction "1_1") (pintype "passive"))
      (node (ref "R703") (pin "1") (pinfunction "1_1") (pintype "passive"))
      (node (ref "R704") (pin "1") (pinfunction "1_1") (pintype "passive"))
    )
    (net (code "47") (name "Net-(C801-Pad1)") (class "Default")
      (node (ref "C801") (pin "1") (pinfunction "1_1") (pintype "passive"))
      (node (ref "R803") (pin "1") (pinfunction "1_1") (pintype "passive"))
      (node (ref "R804") (pin "1") (pinfunction "1_1") (pintype "passive"))
    )
    (net (code "48") (name "Net-(IC2-D+)") (class "Default")
      (node (ref "IC2") (pin "19") (pinfunction "D+_19") (pintype "bidirectional"))
      (node (ref "K1") (pin "2") (pinfunction "2_2") (pintype "passive"))
    )
    (net (code "49") (name "Net-(IC2-D-)") (class "Default")
      (node (ref "IC2") (pin "18") (pinfunction "D-_18") (pintype "bidirectional"))
      (node (ref "K1") (pin "3") (pinfunction "3_3") (pintype "passive"))
    )
    (net (code "50") (name "Net-(IC2-GP6)") (class "Default")
      (node (ref "IC2") (pin "6") (pinfunction "GP6_6") (pintype "bidirectional"))
      (node (ref "LED2") (pin "A") (pinfunction "A_A") (pintype "passive"))
    )
    (net (code "51") (name "Net-(IC2-GP7)") (class "Default")
      (node (ref "IC2") (pin "5") (pinfunction "GP7_5") (pintype "bidirectional"))
      (node (ref "LED1") (pin "A") (pinfunction "A_A") (pintype "passive"))
    )
    (net (code "52") (name "Net-(IC2-OSC1)") (class "Default")
      (node (ref "IC2") (pin "2") (pinfunction "OSC1_2") (pintype "bidirectional"))
      (node (ref "U$9") (pin "1") (pinfunction "1_1") (pintype "passive"))
    )
    (net (code "53") (name "Net-(IC2-OSC2)") (class "Default")
      (node (ref "IC2") (pin "3") (pinfunction "OSC2_3") (pintype "bidirectional"))
      (node (ref "U$9") (pin "3") (pinfunction "3_3") (pintype "passive"))
    )
    (net (code "54") (name "Net-(IC2-VDD)") (class "Default")
      (node (ref "C3") (pin "1") (pinfunction "1_1") (pintype "passive"))
      (node (ref "IC2") (pin "1") (pinfunction "VDD_1") (pintype "power_in"))
      (node (ref "K1") (pin "1") (pinfunction "1_1") (pintype "passive"))
      (node (ref "R2") (pin "2") (pinfunction "2_2") (pintype "passive"))
    )
    (net (code "55") (name "Net-(IC2-VUSB)") (class "Default")
      (node (ref "C2") (pin "1") (pinfunction "1_1") (pintype "passive"))
      (node (ref "IC2") (pin "17") (pinfunction "VUSB_17") (pintype "bidirectional"))
    )
    (net (code "56") (name "Net-(IC2-~{RST})") (class "Default")
      (node (ref "IC2") (pin "4") (pinfunction "~{RST}_4") (pintype "bidirectional"))
      (node (ref "R2") (pin "1") (pinfunction "1_1") (pintype "passive"))
    )
    (net (code "57") (name "Net-(IC3-ADJ)") (class "Default")
      (node (ref "C502") (pin "1") (pinfunction "1_1") (pintype "passive"))
      (node (ref "IC3") (pin "1") (pinfunction "ADJ_1") (pintype "input"))
      (node (ref "R504") (pin "2") (pinfunction "2_2") (pintype "passive"))
    )
    (net (code "58") (name "Net-(IC4-ADJ)") (class "Default")
      (node (ref "C602") (pin "1") (pinfunction "1_1") (pintype "passive"))
      (node (ref "IC4") (pin "1") (pinfunction "ADJ_1") (pintype "input"))
      (node (ref "R604") (pin "2") (pinfunction "2_2") (pintype "passive"))
    )
    (net (code "59") (name "Net-(IC5-ADJ)") (class "Default")
      (node (ref "C702") (pin "1") (pinfunction "1_1") (pintype "passive"))
      (node (ref "IC5") (pin "1") (pinfunction "ADJ_1") (pintype "input"))
      (node (ref "R704") (pin "2") (pinfunction "2_2") (pintype "passive"))
    )
    (net (code "60") (name "Net-(IC5-OUT)") (class "Default")
      (node (ref "IC5") (pin "2") (pinfunction "OUT_2") (pintype "passive"))
      (node (ref "J7") (pin "2") (pinfunction "S_2") (pintype "passive"))
    )
    (net (code "61") (name "Net-(IC6-ADJ)") (class "Default")
      (node (ref "C802") (pin "1") (pinfunction "1_1") (pintype "passive"))
      (node (ref "IC6") (pin "1") (pinfunction "ADJ_1") (pintype "input"))
      (node (ref "R804") (pin "2") (pinfunction "2_2") (pintype "passive"))
    )
    (net (code "62") (name "Net-(IC6-OUT)") (class "Default")
      (node (ref "IC6") (pin "2") (pinfunction "OUT_2") (pintype "passive"))
      (node (ref "J8") (pin "2") (pinfunction "S_2") (pintype "passive"))
    )
    (net (code "63") (name "Net-(IC101-ADJ)") (class "Default")
      (node (ref "C102") (pin "1") (pinfunction "1_1") (pintype "passive"))
      (node (ref "IC101") (pin "1") (pinfunction "ADJ_1") (pintype "input"))
      (node (ref "R104") (pin "2") (pinfunction "2_2") (pintype "passive"))
    )
    (net (code "64") (name "Net-(IC201-ADJ)") (class "Default")
      (node (ref "C202") (pin "1") (pinfunction "1_1") (pintype "passive"))
      (node (ref "IC201") (pin "1") (pinfunction "ADJ_1") (pintype "input"))
      (node (ref "R204") (pin "2") (pinfunction "2_2") (pintype "passive"))
    )
    (net (code "65") (name "Net-(IC301-ADJ)") (class "Default")
      (node (ref "C302") (pin "1") (pinfunction "1_1") (pintype "passive"))
      (node (ref "IC301") (pin "1") (pinfunction "ADJ_1") (pintype "input"))
      (node (ref "R304") (pin "2") (pinfunction "2_2") (pintype "passive"))
    )
    (net (code "66") (name "Net-(IC401-ADJ)") (class "Default")
      (node (ref "C402") (pin "1") (pinfunction "1_1") (pintype "passive"))
      (node (ref "IC401") (pin "1") (pinfunction "ADJ_1") (pintype "input"))
      (node (ref "R404") (pin "2") (pinfunction "2_2") (pintype "passive"))
    )
    (net (code "67") (name "Net-(IC401-OUT)") (class "Default")
      (node (ref "IC401") (pin "2") (pinfunction "OUT_2") (pintype "passive"))
      (node (ref "J4") (pin "2") (pinfunction "S_2") (pintype "passive"))
    )
    (net (code "68") (name "Net-(J2A-S)") (class "Default")
      (node (ref "J2") (pin "1") (pinfunction "S_1") (pintype "passive"))
      (node (ref "R205") (pin "1") (pinfunction "1_1") (pintype "passive"))
      (node (ref "R206") (pin "2") (pinfunction "2_2") (pintype "passive"))
    )
    (net (code "69") (name "Net-(J3A-S)") (class "Default")
      (node (ref "J3") (pin "1") (pinfunction "S_1") (pintype "passive"))
      (node (ref "R305") (pin "1") (pinfunction "1_1") (pintype "passive"))
      (node (ref "R306") (pin "2") (pinfunction "2_2") (pintype "passive"))
    )
    (net (code "70") (name "Net-(J4A-S)") (class "Default")
      (node (ref "J4") (pin "1") (pinfunction "S_1") (pintype "passive"))
      (node (ref "R405") (pin "1") (pinfunction "1_1") (pintype "passive"))
      (node (ref "R406") (pin "2") (pinfunction "2_2") (pintype "passive"))
    )
    (net (code "71") (name "Net-(J5A-S)") (class "Default")
      (node (ref "J5") (pin "1") (pinfunction "S_1") (pintype "passive"))
      (node (ref "R505") (pin "1") (pinfunction "1_1") (pintype "passive"))
      (node (ref "R506") (pin "2") (pinfunction "2_2") (pintype "passive"))
    )
    (net (code "72") (name "Net-(J6A-S)") (class "Default")
      (node (ref "J6") (pin "1") (pinfunction "S_1") (pintype "passive"))
      (node (ref "R605") (pin "1") (pinfunction "1_1") (pintype "passive"))
      (node (ref "R606") (pin "2") (pinfunction "2_2") (pintype "passive"))
    )
    (net (code "73") (name "Net-(J7A-S)") (class "Default")
      (node (ref "J7") (pin "1") (pinfunction "S_1") (pintype "passive"))
      (node (ref "R705") (pin "1") (pinfunction "1_1") (pintype "passive"))
      (node (ref "R706") (pin "2") (pinfunction "2_2") (pintype "passive"))
    )
    (net (code "74") (name "Net-(J8A-S)") (class "Default")
      (node (ref "J8") (pin "1") (pinfunction "S_1") (pintype "passive"))
      (node (ref "R805") (pin "1") (pinfunction "1_1") (pintype "passive"))
      (node (ref "R806") (pin "2") (pinfunction "2_2") (pintype "passive"))
    )
    (net (code "75") (name "Net-(J9A-S)") (class "Default")
      (node (ref "J9") (pin "1") (pinfunction "S_1") (pintype "passive"))
      (node (ref "R105") (pin "1") (pinfunction "1_1") (pintype "passive"))
      (node (ref "R106") (pin "2") (pinfunction "2_2") (pintype "passive"))
    )
    (net (code "76") (name "Net-(J9D-S)") (class "Default")
      (node (ref "J9") (pin "4") (pinfunction "S_4") (pintype "passive"))
      (node (ref "Q1") (pin "C") (pinfunction "C_C") (pintype "passive"))
      (node (ref "R102") (pin "1") (pinfunction "1_1") (pintype "passive"))
      (node (ref "R103") (pin "2") (pinfunction "2_2") (pintype "passive"))
    )
    (net (code "77") (name "Net-(LED1-PadC)") (class "Default")
      (node (ref "LED1") (pin "C") (pinfunction "C_C") (pintype "passive"))
      (node (ref "R3") (pin "1") (pinfunction "1_1") (pintype "passive"))
    )
    (net (code "78") (name "Net-(LED2-PadC)") (class "Default")
      (node (ref "LED2") (pin "C") (pinfunction "C_C") (pintype "passive"))
      (node (ref "R4") (pin "1") (pinfunction "1_1") (pintype "passive"))
    )
    (net (code "79") (name "Net-(Q1-PadB)") (class "Default")
      (node (ref "Q1") (pin "B") (pinfunction "B_B") (pintype "passive"))
      (node (ref "R101") (pin "1") (pinfunction "1_1") (pintype "passive"))
    )
    (net (code "80") (name "Net-(Q2-PadB)") (class "Default")
      (node (ref "Q2") (pin "B") (pinfunction "B_B") (pintype "passive"))
      (node (ref "R201") (pin "1") (pinfunction "1_1") (pintype "passive"))
    )
    (net (code "81") (name "Net-(Q2-PadC)") (class "Default")
      (node (ref "Q2") (pin "C") (pinfunction "C_C") (pintype "passive"))
      (node (ref "R202") (pin "1") (pinfunction "1_1") (pintype "passive"))
      (node (ref "R203") (pin "2") (pinfunction "2_2") (pintype "passive"))
    )
    (net (code "82") (name "Net-(Q3-PadB)") (class "Default")
      (node (ref "Q3") (pin "B") (pinfunction "B_B") (pintype "passive"))
      (node (ref "R301") (pin "1") (pinfunction "1_1") (pintype "passive"))
    )
    (net (code "83") (name "Net-(Q3-PadC)") (class "Default")
      (node (ref "Q3") (pin "C") (pinfunction "C_C") (pintype "passive"))
      (node (ref "R302") (pin "1") (pinfunction "1_1") (pintype "passive"))
      (node (ref "R303") (pin "2") (pinfunction "2_2") (pintype "passive"))
    )
    (net (code "84") (name "Net-(Q4-PadB)") (class "Default")
      (node (ref "Q4") (pin "B") (pinfunction "B_B") (pintype "passive"))
      (node (ref "R401") (pin "1") (pinfunction "1_1") (pintype "passive"))
    )
    (net (code "85") (name "Net-(Q4-PadC)") (class "Default")
      (node (ref "Q4") (pin "C") (pinfunction "C_C") (pintype "passive"))
      (node (ref "R402") (pin "1") (pinfunction "1_1") (pintype "passive"))
      (node (ref "R403") (pin "2") (pinfunction "2_2") (pintype "passive"))
    )
    (net (code "86") (name "Net-(Q5-PadB)") (class "Default")
      (node (ref "Q5") (pin "B") (pinfunction "B_B") (pintype "passive"))
      (node (ref "R501") (pin "1") (pinfunction "1_1") (pintype "passive"))
    )
    (net (code "87") (name "Net-(Q5-PadC)") (class "Default")
      (node (ref "Q5") (pin "C") (pinfunction "C_C") (pintype "passive"))
      (node (ref "R502") (pin "1") (pinfunction "1_1") (pintype "passive"))
      (node (ref "R503") (pin "2") (pinfunction "2_2") (pintype "passive"))
    )
    (net (code "88") (name "Net-(Q6-PadB)") (class "Default")
      (node (ref "Q6") (pin "B") (pinfunction "B_B") (pintype "passive"))
      (node (ref "R601") (pin "1") (pinfunction "1_1") (pintype "passive"))
    )
    (net (code "89") (name "Net-(Q6-PadC)") (class "Default")
      (node (ref "Q6") (pin "C") (pinfunction "C_C") (pintype "passive"))
      (node (ref "R602") (pin "1") (pinfunction "1_1") (pintype "passive"))
      (node (ref "R603") (pin "2") (pinfunction "2_2") (pintype "passive"))
    )
    (net (code "90") (name "Net-(Q7-PadB)") (class "Default")
      (node (ref "Q7") (pin "B") (pinfunction "B_B") (pintype "passive"))
      (node (ref "R701") (pin "1") (pinfunction "1_1") (pintype "passive"))
    )
    (net (code "91") (name "Net-(Q7-PadC)") (class "Default")
      (node (ref "Q7") (pin "C") (pinfunction "C_C") (pintype "passive"))
      (node (ref "R702") (pin "1") (pinfunction "1_1") (pintype "passive"))
      (node (ref "R703") (pin "2") (pinfunction "2_2") (pintype "passive"))
    )
    (net (code "92") (name "Net-(Q8-PadB)") (class "Default")
      (node (ref "Q8") (pin "B") (pinfunction "B_B") (pintype "passive"))
      (node (ref "R801") (pin "1") (pinfunction "1_1") (pintype "passive"))
    )
    (net (code "93") (name "Net-(Q8-PadC)") (class "Default")
      (node (ref "Q8") (pin "C") (pinfunction "C_C") (pintype "passive"))
      (node (ref "R802") (pin "1") (pinfunction "1_1") (pintype "passive"))
      (node (ref "R803") (pin "2") (pinfunction "2_2") (pintype "passive"))
    )
    (net (code "94") (name "RXPIC") (class "Default")
      (node (ref "IC1") (pin "12") (pinfunction "RB5/AN11/RX/DT_12") (pintype "bidirectional"))
      (node (ref "IC2") (pin "10") (pinfunction "TXD_10") (pintype "bidirectional"))
    )
    (net (code "95") (name "SENSE") (class "Default")
      (node (ref "IC1") (pin "19") (pinfunction "RA0/AN0/C1IN+/ICSPDAT_19") (pintype "bidirectional"))
      (node (ref "IC10") (pin "3") (pinfunction "X_3") (pintype "bidirectional"))
      (node (ref "SV3") (pin "4") (pinfunction "4_4") (pintype "passive"))
    )
    (net (code "96") (name "TXPIC") (class "Default")
      (node (ref "IC1") (pin "10") (pinfunction "RB7/TX/CK_10") (pintype "bidirectional"))
      (node (ref "IC2") (pin "12") (pinfunction "RXD_12") (pintype "bidirectional"))
    )
    (net (code "97") (name "unconnected-(IC1-RA4{slash}AN3{slash}T1G_N{slash}OSC2{slash}CLKOUT-Pad3)") (class "Default")
      (node (ref "IC1") (pin "3") (pinfunction "RA4/AN3/T1G_N/OSC2/CLKOUT_3") (pintype "bidirectional"))
    )
    (net (code "98") (name "unconnected-(IC2-GP0-Pad16)") (class "Default")
      (node (ref "IC2") (pin "16") (pinfunction "GP0_16") (pintype "bidirectional"))
    )
    (net (code "99") (name "unconnected-(IC2-GP1-Pad15)") (class "Default")
      (node (ref "IC2") (pin "15") (pinfunction "GP1_15") (pintype "bidirectional"))
    )
    (net (code "100") (name "unconnected-(IC2-GP2-Pad14)") (class "Default")
      (node (ref "IC2") (pin "14") (pinfunction "GP2_14") (pintype "bidirectional"))
    )
    (net (code "101") (name "unconnected-(IC2-GP3-Pad9)") (class "Default")
      (node (ref "IC2") (pin "9") (pinfunction "GP3_9") (pintype "bidirectional"))
    )
    (net (code "102") (name "unconnected-(IC2-GP4-Pad8)") (class "Default")
      (node (ref "IC2") (pin "8") (pinfunction "GP4_8") (pintype "bidirectional"))
    )
    (net (code "103") (name "unconnected-(IC2-GP5-Pad7)") (class "Default")
      (node (ref "IC2") (pin "7") (pinfunction "GP5_7") (pintype "bidirectional"))
    )
    (net (code "104") (name "unconnected-(IC2-~{CTS}-Pad13)") (class "Default")
      (node (ref "IC2") (pin "13") (pinfunction "~{CTS}_13") (pintype "bidirectional"))
    )
    (net (code "105") (name "unconnected-(IC2-~{RTS}-Pad11)") (class "Default")
      (node (ref "IC2") (pin "11") (pinfunction "~{RTS}_11") (pintype "bidirectional"))
    )
    (net (code "106") (name "unconnected-(JP1-Pad3)") (class "Default")
      (node (ref "JP1") (pin "3") (pinfunction "3_3") (pintype "passive"))
    )
    (net (code "107") (name "unconnected-(SV3-Pad6)") (class "Default")
      (node (ref "SV3") (pin "6") (pinfunction "6_6") (pintype "passive"))
    )
  )
)
